# LongLedPcb.net
KiCad netlist of a schematic drawn in Altium Designer
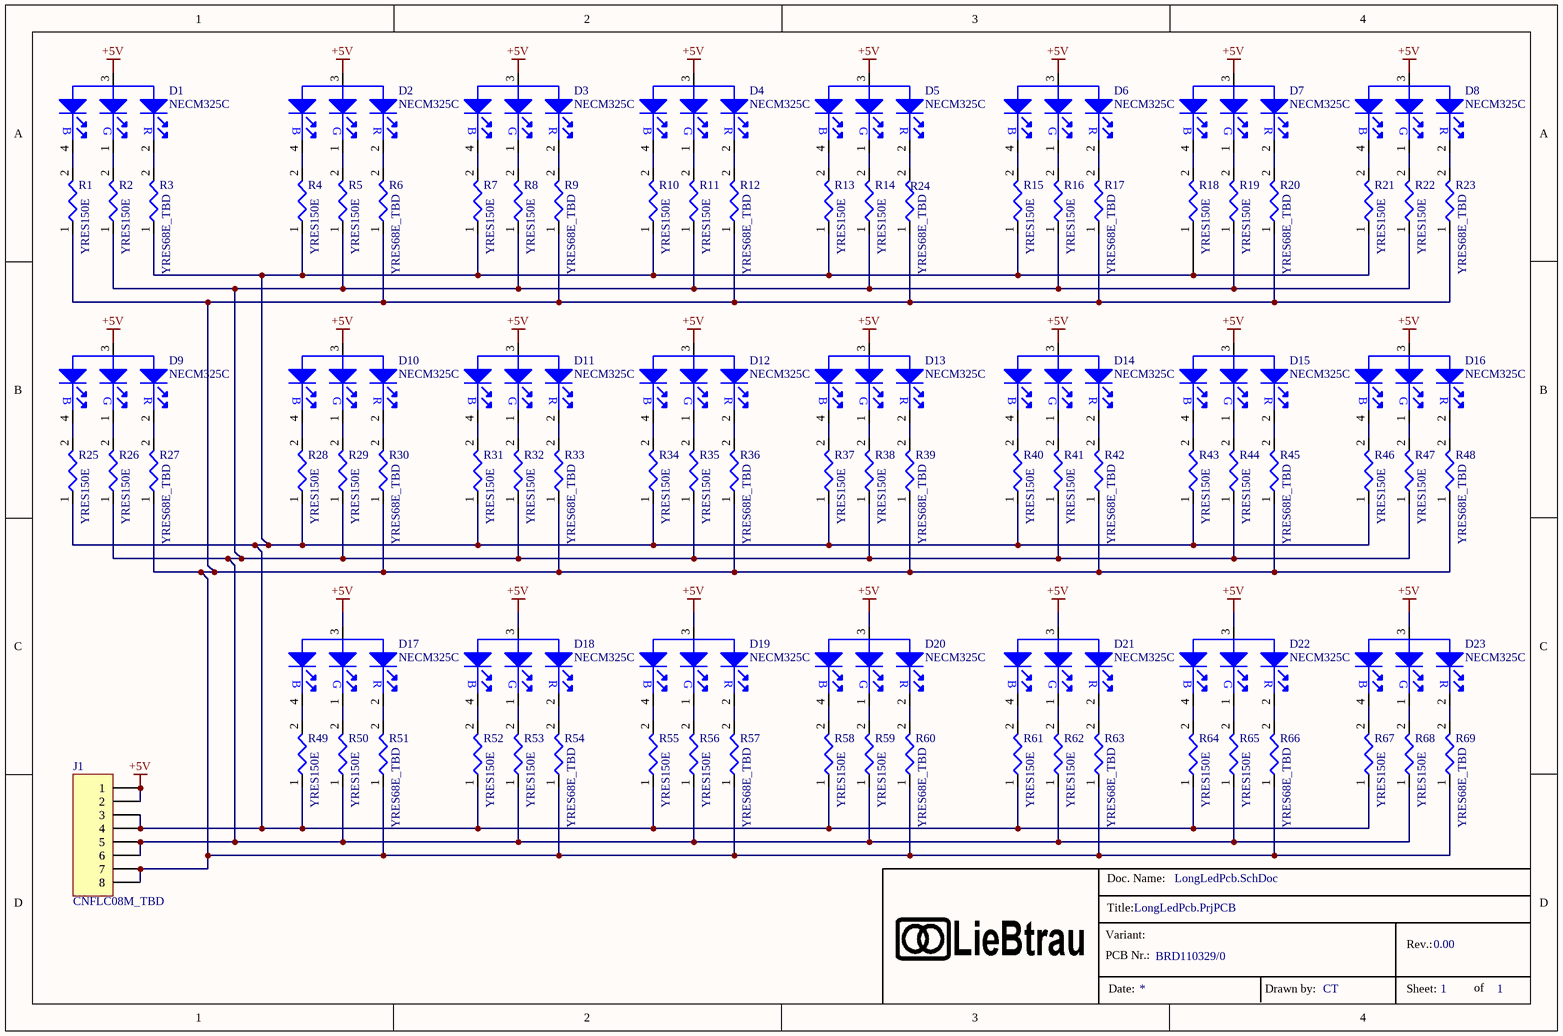
[diagram p0: LongLedPcb.SchDoc]

(export (version "E")
  (design (tool "Eeschema 10.0.6"))
  (components
    (comp (ref "D1")
      (value "NECM325C")
      (footprint "D_NECM325C")
      (libsource (lib "Testing") (part "D_LED_RGB"))
    )
    (comp (ref "D2")
      (value "NECM325C")
      (footprint "D_NECM325C")
      (libsource (lib "Testing") (part "D_LED_RGB"))
    )
    (comp (ref "D3")
      (value "NECM325C")
      (footprint "D_NECM325C")
      (libsource (lib "Testing") (part "D_LED_RGB"))
    )
    (comp (ref "D4")
      (value "NECM325C")
      (footprint "D_NECM325C")
      (libsource (lib "Testing") (part "D_LED_RGB"))
    )
    (comp (ref "D5")
      (value "NECM325C")
      (footprint "D_NECM325C")
      (libsource (lib "Testing") (part "D_LED_RGB"))
    )
    (comp (ref "D6")
      (value "NECM325C")
      (footprint "D_NECM325C")
      (libsource (lib "Testing") (part "D_LED_RGB"))
    )
    (comp (ref "D7")
      (value "NECM325C")
      (footprint "D_NECM325C")
      (libsource (lib "Testing") (part "D_LED_RGB"))
    )
    (comp (ref "D8")
      (value "NECM325C")
      (footprint "D_NECM325C")
      (libsource (lib "Testing") (part "D_LED_RGB"))
    )
    (comp (ref "D9")
      (value "NECM325C")
      (footprint "D_NECM325C")
      (libsource (lib "Testing") (part "D_LED_RGB"))
    )
    (comp (ref "D10")
      (value "NECM325C")
      (footprint "D_NECM325C")
      (libsource (lib "Testing") (part "D_LED_RGB"))
    )
    (comp (ref "D11")
      (value "NECM325C")
      (footprint "D_NECM325C")
      (libsource (lib "Testing") (part "D_LED_RGB"))
    )
    (comp (ref "D12")
      (value "NECM325C")
      (footprint "D_NECM325C")
      (libsource (lib "Testing") (part "D_LED_RGB"))
    )
    (comp (ref "D13")
      (value "NECM325C")
      (footprint "D_NECM325C")
      (libsource (lib "Testing") (part "D_LED_RGB"))
    )
    (comp (ref "D14")
      (value "NECM325C")
      (footprint "D_NECM325C")
      (libsource (lib "Testing") (part "D_LED_RGB"))
    )
    (comp (ref "D15")
      (value "NECM325C")
      (footprint "D_NECM325C")
      (libsource (lib "Testing") (part "D_LED_RGB"))
    )
    (comp (ref "D16")
      (value "NECM325C")
      (footprint "D_NECM325C")
      (libsource (lib "Testing") (part "D_LED_RGB"))
    )
    (comp (ref "D17")
      (value "NECM325C")
      (footprint "D_NECM325C")
      (libsource (lib "Testing") (part "D_LED_RGB"))
    )
    (comp (ref "D18")
      (value "NECM325C")
      (footprint "D_NECM325C")
      (libsource (lib "Testing") (part "D_LED_RGB"))
    )
    (comp (ref "D19")
      (value "NECM325C")
      (footprint "D_NECM325C")
      (libsource (lib "Testing") (part "D_LED_RGB"))
    )
    (comp (ref "D20")
      (value "NECM325C")
      (footprint "D_NECM325C")
      (libsource (lib "Testing") (part "D_LED_RGB"))
    )
    (comp (ref "D21")
      (value "NECM325C")
      (footprint "D_NECM325C")
      (libsource (lib "Testing") (part "D_LED_RGB"))
    )
    (comp (ref "D22")
      (value "NECM325C")
      (footprint "D_NECM325C")
      (libsource (lib "Testing") (part "D_LED_RGB"))
    )
    (comp (ref "D23")
      (value "NECM325C")
      (footprint "D_NECM325C")
      (libsource (lib "Testing") (part "D_LED_RGB"))
    )
    (comp (ref "J1")
      (value "CNFLC08M_TBD")
      (footprint "J_215079-8")
      (fields (field (name "PART NUMBER") "CNFLC08F_TBD"))
      (libsource (lib "Testing") (part "J_8P"))
    )
    (comp (ref "R1")
      (value "YRES150E")
      (footprint "R_1206")
      (description "Resistor")
      (libsource (lib "Testing") (part "R_RES"))
    )
    (comp (ref "R2")
      (value "YRES150E")
      (footprint "R_1206")
      (description "Resistor")
      (libsource (lib "Testing") (part "R_RES"))
    )
    (comp (ref "R3")
      (value "YRES68E_TBD")
      (footprint "R_1206")
      (description "Resistor")
      (libsource (lib "Testing") (part "R_RES"))
    )
    (comp (ref "R4")
      (value "YRES150E")
      (footprint "R_1206")
      (description "Resistor")
      (libsource (lib "Testing") (part "R_RES"))
    )
    (comp (ref "R5")
      (value "YRES150E")
      (footprint "R_1206")
      (description "Resistor")
      (libsource (lib "Testing") (part "R_RES"))
    )
    (comp (ref "R6")
      (value "YRES68E_TBD")
      (footprint "R_1206")
      (description "Resistor")
      (libsource (lib "Testing") (part "R_RES"))
    )
    (comp (ref "R7")
      (value "YRES150E")
      (footprint "R_1206")
      (description "Resistor")
      (libsource (lib "Testing") (part "R_RES"))
    )
    (comp (ref "R8")
      (value "YRES150E")
      (footprint "R_1206")
      (description "Resistor")
      (libsource (lib "Testing") (part "R_RES"))
    )
    (comp (ref "R9")
      (value "YRES68E_TBD")
      (footprint "R_1206")
      (description "Resistor")
      (libsource (lib "Testing") (part "R_RES"))
    )
    (comp (ref "R10")
      (value "YRES150E")
      (footprint "R_1206")
      (description "Resistor")
      (libsource (lib "Testing") (part "R_RES"))
    )
    (comp (ref "R11")
      (value "YRES150E")
      (footprint "R_1206")
      (description "Resistor")
      (libsource (lib "Testing") (part "R_RES"))
    )
    (comp (ref "R12")
      (value "YRES68E_TBD")
      (footprint "R_1206")
      (description "Resistor")
      (libsource (lib "Testing") (part "R_RES"))
    )
    (comp (ref "R13")
      (value "YRES150E")
      (footprint "R_1206")
      (description "Resistor")
      (libsource (lib "Testing") (part "R_RES"))
    )
    (comp (ref "R14")
      (value "YRES150E")
      (footprint "R_1206")
      (description "Resistor")
      (libsource (lib "Testing") (part "R_RES"))
    )
    (comp (ref "R15")
      (value "YRES150E")
      (footprint "R_1206")
      (description "Resistor")
      (libsource (lib "Testing") (part "R_RES"))
    )
    (comp (ref "R16")
      (value "YRES150E")
      (footprint "R_1206")
      (description "Resistor")
      (libsource (lib "Testing") (part "R_RES"))
    )
    (comp (ref "R17")
      (value "YRES68E_TBD")
      (footprint "R_1206")
      (description "Resistor")
      (libsource (lib "Testing") (part "R_RES"))
    )
    (comp (ref "R18")
      (value "YRES150E")
      (footprint "R_1206")
      (description "Resistor")
      (libsource (lib "Testing") (part "R_RES"))
    )
    (comp (ref "R19")
      (value "YRES150E")
      (footprint "R_1206")
      (description "Resistor")
      (libsource (lib "Testing") (part "R_RES"))
    )
    (comp (ref "R20")
      (value "YRES68E_TBD")
      (footprint "R_1206")
      (description "Resistor")
      (libsource (lib "Testing") (part "R_RES"))
    )
    (comp (ref "R21")
      (value "YRES150E")
      (footprint "R_1206")
      (description "Resistor")
      (libsource (lib "Testing") (part "R_RES"))
    )
    (comp (ref "R22")
      (value "YRES150E")
      (footprint "R_1206")
      (description "Resistor")
      (libsource (lib "Testing") (part "R_RES"))
    )
    (comp (ref "R23")
      (value "YRES68E_TBD")
      (footprint "R_1206")
      (description "Resistor")
      (libsource (lib "Testing") (part "R_RES"))
    )
    (comp (ref "R24")
      (value "YRES68E_TBD")
      (footprint "R_1206")
      (description "Resistor")
      (libsource (lib "Testing") (part "R_RES"))
    )
    (comp (ref "R25")
      (value "YRES150E")
      (footprint "R_1206")
      (description "Resistor")
      (libsource (lib "Testing") (part "R_RES"))
    )
    (comp (ref "R26")
      (value "YRES150E")
      (footprint "R_1206")
      (description "Resistor")
      (libsource (lib "Testing") (part "R_RES"))
    )
    (comp (ref "R27")
      (value "YRES68E_TBD")
      (footprint "R_1206")
      (description "Resistor")
      (libsource (lib "Testing") (part "R_RES"))
    )
    (comp (ref "R28")
      (value "YRES150E")
      (footprint "R_1206")
      (description "Resistor")
      (libsource (lib "Testing") (part "R_RES"))
    )
    (comp (ref "R29")
      (value "YRES150E")
      (footprint "R_1206")
      (description "Resistor")
      (libsource (lib "Testing") (part "R_RES"))
    )
    (comp (ref "R30")
      (value "YRES68E_TBD")
      (footprint "R_1206")
      (description "Resistor")
      (libsource (lib "Testing") (part "R_RES"))
    )
    (comp (ref "R31")
      (value "YRES150E")
      (footprint "R_1206")
      (description "Resistor")
      (libsource (lib "Testing") (part "R_RES"))
    )
    (comp (ref "R32")
      (value "YRES150E")
      (footprint "R_1206")
      (description "Resistor")
      (libsource (lib "Testing") (part "R_RES"))
    )
    (comp (ref "R33")
      (value "YRES68E_TBD")
      (footprint "R_1206")
      (description "Resistor")
      (libsource (lib "Testing") (part "R_RES"))
    )
    (comp (ref "R34")
      (value "YRES150E")
      (footprint "R_1206")
      (description "Resistor")
      (libsource (lib "Testing") (part "R_RES"))
    )
    (comp (ref "R35")
      (value "YRES150E")
      (footprint "R_1206")
      (description "Resistor")
      (libsource (lib "Testing") (part "R_RES"))
    )
    (comp (ref "R36")
      (value "YRES68E_TBD")
      (footprint "R_1206")
      (description "Resistor")
      (libsource (lib "Testing") (part "R_RES"))
    )
    (comp (ref "R37")
      (value "YRES150E")
      (footprint "R_1206")
      (description "Resistor")
      (libsource (lib "Testing") (part "R_RES"))
    )
    (comp (ref "R38")
      (value "YRES150E")
      (footprint "R_1206")
      (description "Resistor")
      (libsource (lib "Testing") (part "R_RES"))
    )
    (comp (ref "R39")
      (value "YRES68E_TBD")
      (footprint "R_1206")
      (description "Resistor")
      (libsource (lib "Testing") (part "R_RES"))
    )
    (comp (ref "R40")
      (value "YRES150E")
      (footprint "R_1206")
      (description "Resistor")
      (libsource (lib "Testing") (part "R_RES"))
    )
    (comp (ref "R41")
      (value "YRES150E")
      (footprint "R_1206")
      (description "Resistor")
      (libsource (lib "Testing") (part "R_RES"))
    )
    (comp (ref "R42")
      (value "YRES68E_TBD")
      (footprint "R_1206")
      (description "Resistor")
      (libsource (lib "Testing") (part "R_RES"))
    )
    (comp (ref "R43")
      (value "YRES150E")
      (footprint "R_1206")
      (description "Resistor")
      (libsource (lib "Testing") (part "R_RES"))
    )
    (comp (ref "R44")
      (value "YRES150E")
      (footprint "R_1206")
      (description "Resistor")
      (libsource (lib "Testing") (part "R_RES"))
    )
    (comp (ref "R45")
      (value "YRES68E_TBD")
      (footprint "R_1206")
      (description "Resistor")
      (libsource (lib "Testing") (part "R_RES"))
    )
    (comp (ref "R46")
      (value "YRES150E")
      (footprint "R_1206")
      (description "Resistor")
      (libsource (lib "Testing") (part "R_RES"))
    )
    (comp (ref "R47")
      (value "YRES150E")
      (footprint "R_1206")
      (description "Resistor")
      (libsource (lib "Testing") (part "R_RES"))
    )
    (comp (ref "R48")
      (value "YRES68E_TBD")
      (footprint "R_1206")
      (description "Resistor")
      (libsource (lib "Testing") (part "R_RES"))
    )
    (comp (ref "R49")
      (value "YRES150E")
      (footprint "R_1206")
      (description "Resistor")
      (libsource (lib "Testing") (part "R_RES"))
    )
    (comp (ref "R50")
      (value "YRES150E")
      (footprint "R_1206")
      (description "Resistor")
      (libsource (lib "Testing") (part "R_RES"))
    )
    (comp (ref "R51")
      (value "YRES68E_TBD")
      (footprint "R_1206")
      (description "Resistor")
      (libsource (lib "Testing") (part "R_RES"))
    )
    (comp (ref "R52")
      (value "YRES150E")
      (footprint "R_1206")
      (description "Resistor")
      (libsource (lib "Testing") (part "R_RES"))
    )
    (comp (ref "R53")
      (value "YRES150E")
      (footprint "R_1206")
      (description "Resistor")
      (libsource (lib "Testing") (part "R_RES"))
    )
    (comp (ref "R54")
      (value "YRES68E_TBD")
      (footprint "R_1206")
      (description "Resistor")
      (libsource (lib "Testing") (part "R_RES"))
    )
    (comp (ref "R55")
      (value "YRES150E")
      (footprint "R_1206")
      (description "Resistor")
      (libsource (lib "Testing") (part "R_RES"))
    )
    (comp (ref "R56")
      (value "YRES150E")
      (footprint "R_1206")
      (description "Resistor")
      (libsource (lib "Testing") (part "R_RES"))
    )
    (comp (ref "R57")
      (value "YRES68E_TBD")
      (footprint "R_1206")
      (description "Resistor")
      (libsource (lib "Testing") (part "R_RES"))
    )
    (comp (ref "R58")
      (value "YRES150E")
      (footprint "R_1206")
      (description "Resistor")
      (libsource (lib "Testing") (part "R_RES"))
    )
    (comp (ref "R59")
      (value "YRES150E")
      (footprint "R_1206")
      (description "Resistor")
      (libsource (lib "Testing") (part "R_RES"))
    )
    (comp (ref "R60")
      (value "YRES68E_TBD")
      (footprint "R_1206")
      (description "Resistor")
      (libsource (lib "Testing") (part "R_RES"))
    )
    (comp (ref "R61")
      (value "YRES150E")
      (footprint "R_1206")
      (description "Resistor")
      (libsource (lib "Testing") (part "R_RES"))
    )
    (comp (ref "R62")
      (value "YRES150E")
      (footprint "R_1206")
      (description "Resistor")
      (libsource (lib "Testing") (part "R_RES"))
    )
    (comp (ref "R63")
      (value "YRES68E_TBD")
      (footprint "R_1206")
      (description "Resistor")
      (libsource (lib "Testing") (part "R_RES"))
    )
    (comp (ref "R64")
      (value "YRES150E")
      (footprint "R_1206")
      (description "Resistor")
      (libsource (lib "Testing") (part "R_RES"))
    )
    (comp (ref "R65")
      (value "YRES150E")
      (footprint "R_1206")
      (description "Resistor")
      (libsource (lib "Testing") (part "R_RES"))
    )
    (comp (ref "R66")
      (value "YRES68E_TBD")
      (footprint "R_1206")
      (description "Resistor")
      (libsource (lib "Testing") (part "R_RES"))
    )
    (comp (ref "R67")
      (value "YRES150E")
      (footprint "R_1206")
      (description "Resistor")
      (libsource (lib "Testing") (part "R_RES"))
    )
    (comp (ref "R68")
      (value "YRES150E")
      (footprint "R_1206")
      (description "Resistor")
      (libsource (lib "Testing") (part "R_RES"))
    )
    (comp (ref "R69")
      (value "YRES68E_TBD")
      (footprint "R_1206")
      (description "Resistor")
      (libsource (lib "Testing") (part "R_RES"))
    )
  )
  (nets
    (net (code "1") (name "+5V") (class "Default")
      (node (ref "D1") (pin "3") (pinfunction "A_3") (pintype "passive"))
      (node (ref "D10") (pin "3") (pinfunction "A_3") (pintype "passive"))
      (node (ref "D11") (pin "3") (pinfunction "A_3") (pintype "passive"))
      (node (ref "D12") (pin "3") (pinfunction "A_3") (pintype "passive"))
      (node (ref "D13") (pin "3") (pinfunction "A_3") (pintype "passive"))
      (node (ref "D14") (pin "3") (pinfunction "A_3") (pintype "passive"))
      (node (ref "D15") (pin "3") (pinfunction "A_3") (pintype "passive"))
      (node (ref "D16") (pin "3") (pinfunction "A_3") (pintype "passive"))
      (node (ref "D17") (pin "3") (pinfunction "A_3") (pintype "passive"))
      (node (ref "D18") (pin "3") (pinfunction "A_3") (pintype "passive"))
      (node (ref "D19") (pin "3") (pinfunction "A_3") (pintype "passive"))
      (node (ref "D2") (pin "3") (pinfunction "A_3") (pintype "passive"))
      (node (ref "D20") (pin "3") (pinfunction "A_3") (pintype "passive"))
      (node (ref "D21") (pin "3") (pinfunction "A_3") (pintype "passive"))
      (node (ref "D22") (pin "3") (pinfunction "A_3") (pintype "passive"))
      (node (ref "D23") (pin "3") (pinfunction "A_3") (pintype "passive"))
      (node (ref "D3") (pin "3") (pinfunction "A_3") (pintype "passive"))
      (node (ref "D4") (pin "3") (pinfunction "A_3") (pintype "passive"))
      (node (ref "D5") (pin "3") (pinfunction "A_3") (pintype "passive"))
      (node (ref "D6") (pin "3") (pinfunction "A_3") (pintype "passive"))
      (node (ref "D7") (pin "3") (pinfunction "A_3") (pintype "passive"))
      (node (ref "D8") (pin "3") (pinfunction "A_3") (pintype "passive"))
      (node (ref "D9") (pin "3") (pinfunction "A_3") (pintype "passive"))
      (node (ref "J1") (pin "1") (pinfunction "1_1") (pintype "passive"))
      (node (ref "J1") (pin "2") (pinfunction "2_2") (pintype "passive"))
    )
    (net (code "2") (name "Net-(D1-C-Pad1)") (class "Default")
      (node (ref "D1") (pin "1") (pinfunction "C_1") (pintype "passive"))
      (node (ref "R2") (pin "2") (pinfunction "2_2") (pintype "passive"))
    )
    (net (code "3") (name "Net-(D1-C-Pad2)") (class "Default")
      (node (ref "D1") (pin "2") (pinfunction "C_2") (pintype "passive"))
      (node (ref "R3") (pin "2") (pinfunction "2_2") (pintype "passive"))
    )
    (net (code "4") (name "Net-(D1-C-Pad4)") (class "Default")
      (node (ref "D1") (pin "4") (pinfunction "C_4") (pintype "passive"))
      (node (ref "R1") (pin "2") (pinfunction "2_2") (pintype "passive"))
    )
    (net (code "5") (name "Net-(D2-C-Pad1)") (class "Default")
      (node (ref "D2") (pin "1") (pinfunction "C_1") (pintype "passive"))
      (node (ref "R5") (pin "2") (pinfunction "2_2") (pintype "passive"))
    )
    (net (code "6") (name "Net-(D2-C-Pad2)") (class "Default")
      (node (ref "D2") (pin "2") (pinfunction "C_2") (pintype "passive"))
      (node (ref "R6") (pin "2") (pinfunction "2_2") (pintype "passive"))
    )
    (net (code "7") (name "Net-(D2-C-Pad4)") (class "Default")
      (node (ref "D2") (pin "4") (pinfunction "C_4") (pintype "passive"))
      (node (ref "R4") (pin "2") (pinfunction "2_2") (pintype "passive"))
    )
    (net (code "8") (name "Net-(D3-C-Pad1)") (class "Default")
      (node (ref "D3") (pin "1") (pinfunction "C_1") (pintype "passive"))
      (node (ref "R8") (pin "2") (pinfunction "2_2") (pintype "passive"))
    )
    (net (code "9") (name "Net-(D3-C-Pad2)") (class "Default")
      (node (ref "D3") (pin "2") (pinfunction "C_2") (pintype "passive"))
      (node (ref "R9") (pin "2") (pinfunction "2_2") (pintype "passive"))
    )
    (net (code "10") (name "Net-(D3-C-Pad4)") (class "Default")
      (node (ref "D3") (pin "4") (pinfunction "C_4") (pintype "passive"))
      (node (ref "R7") (pin "2") (pinfunction "2_2") (pintype "passive"))
    )
    (net (code "11") (name "Net-(D4-C-Pad1)") (class "Default")
      (node (ref "D4") (pin "1") (pinfunction "C_1") (pintype "passive"))
      (node (ref "R11") (pin "2") (pinfunction "2_2") (pintype "passive"))
    )
    (net (code "12") (name "Net-(D4-C-Pad2)") (class "Default")
      (node (ref "D4") (pin "2") (pinfunction "C_2") (pintype "passive"))
      (node (ref "R12") (pin "2") (pinfunction "2_2") (pintype "passive"))
    )
    (net (code "13") (name "Net-(D4-C-Pad4)") (class "Default")
      (node (ref "D4") (pin "4") (pinfunction "C_4") (pintype "passive"))
      (node (ref "R10") (pin "2") (pinfunction "2_2") (pintype "passive"))
    )
    (net (code "14") (name "Net-(D5-C-Pad1)") (class "Default")
      (node (ref "D5") (pin "1") (pinfunction "C_1") (pintype "passive"))
      (node (ref "R14") (pin "2") (pinfunction "2_2") (pintype "passive"))
    )
    (net (code "15") (name "Net-(D5-C-Pad2)") (class "Default")
      (node (ref "D5") (pin "2") (pinfunction "C_2") (pintype "passive"))
      (node (ref "R24") (pin "2") (pinfunction "2_2") (pintype "passive"))
    )
    (net (code "16") (name "Net-(D5-C-Pad4)") (class "Default")
      (node (ref "D5") (pin "4") (pinfunction "C_4") (pintype "passive"))
      (node (ref "R13") (pin "2") (pinfunction "2_2") (pintype "passive"))
    )
    (net (code "17") (name "Net-(D6-C-Pad1)") (class "Default")
      (node (ref "D6") (pin "1") (pinfunction "C_1") (pintype "passive"))
      (node (ref "R16") (pin "2") (pinfunction "2_2") (pintype "passive"))
    )
    (net (code "18") (name "Net-(D6-C-Pad2)") (class "Default")
      (node (ref "D6") (pin "2") (pinfunction "C_2") (pintype "passive"))
      (node (ref "R17") (pin "2") (pinfunction "2_2") (pintype "passive"))
    )
    (net (code "19") (name "Net-(D6-C-Pad4)") (class "Default")
      (node (ref "D6") (pin "4") (pinfunction "C_4") (pintype "passive"))
      (node (ref "R15") (pin "2") (pinfunction "2_2") (pintype "passive"))
    )
    (net (code "20") (name "Net-(D7-C-Pad1)") (class "Default")
      (node (ref "D7") (pin "1") (pinfunction "C_1") (pintype "passive"))
      (node (ref "R19") (pin "2") (pinfunction "2_2") (pintype "passive"))
    )
    (net (code "21") (name "Net-(D7-C-Pad2)") (class "Default")
      (node (ref "D7") (pin "2") (pinfunction "C_2") (pintype "passive"))
      (node (ref "R20") (pin "2") (pinfunction "2_2") (pintype "passive"))
    )
    (net (code "22") (name "Net-(D7-C-Pad4)") (class "Default")
      (node (ref "D7") (pin "4") (pinfunction "C_4") (pintype "passive"))
      (node (ref "R18") (pin "2") (pinfunction "2_2") (pintype "passive"))
    )
    (net (code "23") (name "Net-(D8-C-Pad1)") (class "Default")
      (node (ref "D8") (pin "1") (pinfunction "C_1") (pintype "passive"))
      (node (ref "R22") (pin "2") (pinfunction "2_2") (pintype "passive"))
    )
    (net (code "24") (name "Net-(D8-C-Pad2)") (class "Default")
      (node (ref "D8") (pin "2") (pinfunction "C_2") (pintype "passive"))
      (node (ref "R23") (pin "2") (pinfunction "2_2") (pintype "passive"))
    )
    (net (code "25") (name "Net-(D8-C-Pad4)") (class "Default")
      (node (ref "D8") (pin "4") (pinfunction "C_4") (pintype "passive"))
      (node (ref "R21") (pin "2") (pinfunction "2_2") (pintype "passive"))
    )
    (net (code "26") (name "Net-(D9-C-Pad1)") (class "Default")
      (node (ref "D9") (pin "1") (pinfunction "C_1") (pintype "passive"))
      (node (ref "R26") (pin "2") (pinfunction "2_2") (pintype "passive"))
    )
    (net (code "27") (name "Net-(D9-C-Pad2)") (class "Default")
      (node (ref "D9") (pin "2") (pinfunction "C_2") (pintype "passive"))
      (node (ref "R27") (pin "2") (pinfunction "2_2") (pintype "passive"))
    )
    (net (code "28") (name "Net-(D9-C-Pad4)") (class "Default")
      (node (ref "D9") (pin "4") (pinfunction "C_4") (pintype "passive"))
      (node (ref "R25") (pin "2") (pinfunction "2_2") (pintype "passive"))
    )
    (net (code "29") (name "Net-(D10-C-Pad1)") (class "Default")
      (node (ref "D10") (pin "1") (pinfunction "C_1") (pintype "passive"))
      (node (ref "R29") (pin "2") (pinfunction "2_2") (pintype "passive"))
    )
    (net (code "30") (name "Net-(D10-C-Pad2)") (class "Default")
      (node (ref "D10") (pin "2") (pinfunction "C_2") (pintype "passive"))
      (node (ref "R30") (pin "2") (pinfunction "2_2") (pintype "passive"))
    )
    (net (code "31") (name "Net-(D10-C-Pad4)") (class "Default")
      (node (ref "D10") (pin "4") (pinfunction "C_4") (pintype "passive"))
      (node (ref "R28") (pin "2") (pinfunction "2_2") (pintype "passive"))
    )
    (net (code "32") (name "Net-(D11-C-Pad1)") (class "Default")
      (node (ref "D11") (pin "1") (pinfunction "C_1") (pintype "passive"))
      (node (ref "R32") (pin "2") (pinfunction "2_2") (pintype "passive"))
    )
    (net (code "33") (name "Net-(D11-C-Pad2)") (class "Default")
      (node (ref "D11") (pin "2") (pinfunction "C_2") (pintype "passive"))
      (node (ref "R33") (pin "2") (pinfunction "2_2") (pintype "passive"))
    )
    (net (code "34") (name "Net-(D11-C-Pad4)") (class "Default")
      (node (ref "D11") (pin "4") (pinfunction "C_4") (pintype "passive"))
      (node (ref "R31") (pin "2") (pinfunction "2_2") (pintype "passive"))
    )
    (net (code "35") (name "Net-(D12-C-Pad1)") (class "Default")
      (node (ref "D12") (pin "1") (pinfunction "C_1") (pintype "passive"))
      (node (ref "R35") (pin "2") (pinfunction "2_2") (pintype "passive"))
    )
    (net (code "36") (name "Net-(D12-C-Pad2)") (class "Default")
      (node (ref "D12") (pin "2") (pinfunction "C_2") (pintype "passive"))
      (node (ref "R36") (pin "2") (pinfunction "2_2") (pintype "passive"))
    )
    (net (code "37") (name "Net-(D12-C-Pad4)") (class "Default")
      (node (ref "D12") (pin "4") (pinfunction "C_4") (pintype "passive"))
      (node (ref "R34") (pin "2") (pinfunction "2_2") (pintype "passive"))
    )
    (net (code "38") (name "Net-(D13-C-Pad1)") (class "Default")
      (node (ref "D13") (pin "1") (pinfunction "C_1") (pintype "passive"))
      (node (ref "R38") (pin "2") (pinfunction "2_2") (pintype "passive"))
    )
    (net (code "39") (name "Net-(D13-C-Pad2)") (class "Default")
      (node (ref "D13") (pin "2") (pinfunction "C_2") (pintype "passive"))
      (node (ref "R39") (pin "2") (pinfunction "2_2") (pintype "passive"))
    )
    (net (code "40") (name "Net-(D13-C-Pad4)") (class "Default")
      (node (ref "D13") (pin "4") (pinfunction "C_4") (pintype "passive"))
      (node (ref "R37") (pin "2") (pinfunction "2_2") (pintype "passive"))
    )
    (net (code "41") (name "Net-(D14-C-Pad1)") (class "Default")
      (node (ref "D14") (pin "1") (pinfunction "C_1") (pintype "passive"))
      (node (ref "R41") (pin "2") (pinfunction "2_2") (pintype "passive"))
    )
    (net (code "42") (name "Net-(D14-C-Pad2)") (class "Default")
      (node (ref "D14") (pin "2") (pinfunction "C_2") (pintype "passive"))
      (node (ref "R42") (pin "2") (pinfunction "2_2") (pintype "passive"))
    )
    (net (code "43") (name "Net-(D14-C-Pad4)") (class "Default")
      (node (ref "D14") (pin "4") (pinfunction "C_4") (pintype "passive"))
      (node (ref "R40") (pin "2") (pinfunction "2_2") (pintype "passive"))
    )
    (net (code "44") (name "Net-(D15-C-Pad1)") (class "Default")
      (node (ref "D15") (pin "1") (pinfunction "C_1") (pintype "passive"))
      (node (ref "R44") (pin "2") (pinfunction "2_2") (pintype "passive"))
    )
    (net (code "45") (name "Net-(D15-C-Pad2)") (class "Default")
      (node (ref "D15") (pin "2") (pinfunction "C_2") (pintype "passive"))
      (node (ref "R45") (pin "2") (pinfunction "2_2") (pintype "passive"))
    )
    (net (code "46") (name "Net-(D15-C-Pad4)") (class "Default")
      (node (ref "D15") (pin "4") (pinfunction "C_4") (pintype "passive"))
      (node (ref "R43") (pin "2") (pinfunction "2_2") (pintype "passive"))
    )
    (net (code "47") (name "Net-(D16-C-Pad1)") (class "Default")
      (node (ref "D16") (pin "1") (pinfunction "C_1") (pintype "passive"))
      (node (ref "R47") (pin "2") (pinfunction "2_2") (pintype "passive"))
    )
    (net (code "48") (name "Net-(D16-C-Pad2)") (class "Default")
      (node (ref "D16") (pin "2") (pinfunction "C_2") (pintype "passive"))
      (node (ref "R48") (pin "2") (pinfunction "2_2") (pintype "passive"))
    )
    (net (code "49") (name "Net-(D16-C-Pad4)") (class "Default")
      (node (ref "D16") (pin "4") (pinfunction "C_4") (pintype "passive"))
      (node (ref "R46") (pin "2") (pinfunction "2_2") (pintype "passive"))
    )
    (net (code "50") (name "Net-(D17-C-Pad1)") (class "Default")
      (node (ref "D17") (pin "1") (pinfunction "C_1") (pintype "passive"))
      (node (ref "R50") (pin "2") (pinfunction "2_2") (pintype "passive"))
    )
    (net (code "51") (name "Net-(D17-C-Pad2)") (class "Default")
      (node (ref "D17") (pin "2") (pinfunction "C_2") (pintype "passive"))
      (node (ref "R51") (pin "2") (pinfunction "2_2") (pintype "passive"))
    )
    (net (code "52") (name "Net-(D17-C-Pad4)") (class "Default")
      (node (ref "D17") (pin "4") (pinfunction "C_4") (pintype "passive"))
      (node (ref "R49") (pin "2") (pinfunction "2_2") (pintype "passive"))
    )
    (net (code "53") (name "Net-(D18-C-Pad1)") (class "Default")
      (node (ref "D18") (pin "1") (pinfunction "C_1") (pintype "passive"))
      (node (ref "R53") (pin "2") (pinfunction "2_2") (pintype "passive"))
    )
    (net (code "54") (name "Net-(D18-C-Pad2)") (class "Default")
      (node (ref "D18") (pin "2") (pinfunction "C_2") (pintype "passive"))
      (node (ref "R54") (pin "2") (pinfunction "2_2") (pintype "passive"))
    )
    (net (code "55") (name "Net-(D18-C-Pad4)") (class "Default")
      (node (ref "D18") (pin "4") (pinfunction "C_4") (pintype "passive"))
      (node (ref "R52") (pin "2") (pinfunction "2_2") (pintype "passive"))
    )
    (net (code "56") (name "Net-(D19-C-Pad1)") (class "Default")
      (node (ref "D19") (pin "1") (pinfunction "C_1") (pintype "passive"))
      (node (ref "R56") (pin "2") (pinfunction "2_2") (pintype "passive"))
    )
    (net (code "57") (name "Net-(D19-C-Pad2)") (class "Default")
      (node (ref "D19") (pin "2") (pinfunction "C_2") (pintype "passive"))
      (node (ref "R57") (pin "2") (pinfunction "2_2") (pintype "passive"))
    )
    (net (code "58") (name "Net-(D19-C-Pad4)") (class "Default")
      (node (ref "D19") (pin "4") (pinfunction "C_4") (pintype "passive"))
      (node (ref "R55") (pin "2") (pinfunction "2_2") (pintype "passive"))
    )
    (net (code "59") (name "Net-(D20-C-Pad1)") (class "Default")
      (node (ref "D20") (pin "1") (pinfunction "C_1") (pintype "passive"))
      (node (ref "R59") (pin "2") (pinfunction "2_2") (pintype "passive"))
    )
    (net (code "60") (name "Net-(D20-C-Pad2)") (class "Default")
      (node (ref "D20") (pin "2") (pinfunction "C_2") (pintype "passive"))
      (node (ref "R60") (pin "2") (pinfunction "2_2") (pintype "passive"))
    )
    (net (code "61") (name "Net-(D20-C-Pad4)") (class "Default")
      (node (ref "D20") (pin "4") (pinfunction "C_4") (pintype "passive"))
      (node (ref "R58") (pin "2") (pinfunction "2_2") (pintype "passive"))
    )
    (net (code "62") (name "Net-(D21-C-Pad1)") (class "Default")
      (node (ref "D21") (pin "1") (pinfunction "C_1") (pintype "passive"))
      (node (ref "R62") (pin "2") (pinfunction "2_2") (pintype "passive"))
    )
    (net (code "63") (name "Net-(D21-C-Pad2)") (class "Default")
      (node (ref "D21") (pin "2") (pinfunction "C_2") (pintype "passive"))
      (node (ref "R63") (pin "2") (pinfunction "2_2") (pintype "passive"))
    )
    (net (code "64") (name "Net-(D21-C-Pad4)") (class "Default")
      (node (ref "D21") (pin "4") (pinfunction "C_4") (pintype "passive"))
      (node (ref "R61") (pin "2") (pinfunction "2_2") (pintype "passive"))
    )
    (net (code "65") (name "Net-(D22-C-Pad1)") (class "Default")
      (node (ref "D22") (pin "1") (pinfunction "C_1") (pintype "passive"))
      (node (ref "R65") (pin "2") (pinfunction "2_2") (pintype "passive"))
    )
    (net (code "66") (name "Net-(D22-C-Pad2)") (class "Default")
      (node (ref "D22") (pin "2") (pinfunction "C_2") (pintype "passive"))
      (node (ref "R66") (pin "2") (pinfunction "2_2") (pintype "passive"))
    )
    (net (code "67") (name "Net-(D22-C-Pad4)") (class "Default")
      (node (ref "D22") (pin "4") (pinfunction "C_4") (pintype "passive"))
      (node (ref "R64") (pin "2") (pinfunction "2_2") (pintype "passive"))
    )
    (net (code "68") (name "Net-(D23-C-Pad1)") (class "Default")
      (node (ref "D23") (pin "1") (pinfunction "C_1") (pintype "passive"))
      (node (ref "R68") (pin "2") (pinfunction "2_2") (pintype "passive"))
    )
    (net (code "69") (name "Net-(D23-C-Pad2)") (class "Default")
      (node (ref "D23") (pin "2") (pinfunction "C_2") (pintype "passive"))
      (node (ref "R69") (pin "2") (pinfunction "2_2") (pintype "passive"))
    )
    (net (code "70") (name "Net-(D23-C-Pad4)") (class "Default")
      (node (ref "D23") (pin "4") (pinfunction "C_4") (pintype "passive"))
      (node (ref "R67") (pin "2") (pinfunction "2_2") (pintype "passive"))
    )
    (net (code "71") (name "Net-(J1-Pad3)") (class "Default")
      (node (ref "J1") (pin "3") (pinfunction "3_3") (pintype "passive"))
      (node (ref "J1") (pin "4") (pinfunction "4_4") (pintype "passive"))
      (node (ref "R10") (pin "1") (pinfunction "1_1") (pintype "passive"))
      (node (ref "R13") (pin "1") (pinfunction "1_1") (pintype "passive"))
      (node (ref "R15") (pin "1") (pinfunction "1_1") (pintype "passive"))
      (node (ref "R18") (pin "1") (pinfunction "1_1") (pintype "passive"))
      (node (ref "R21") (pin "1") (pinfunction "1_1") (pintype "passive"))
      (node (ref "R25") (pin "1") (pinfunction "1_1") (pintype "passive"))
      (node (ref "R28") (pin "1") (pinfunction "1_1") (pintype "passive"))
      (node (ref "R3") (pin "1") (pinfunction "1_1") (pintype "passive"))
      (node (ref "R31") (pin "1") (pinfunction "1_1") (pintype "passive"))
      (node (ref "R34") (pin "1") (pinfunction "1_1") (pintype "passive"))
      (node (ref "R37") (pin "1") (pinfunction "1_1") (pintype "passive"))
      (node (ref "R4") (pin "1") (pinfunction "1_1") (pintype "passive"))
      (node (ref "R40") (pin "1") (pinfunction "1_1") (pintype "passive"))
      (node (ref "R43") (pin "1") (pinfunction "1_1") (pintype "passive"))
      (node (ref "R46") (pin "1") (pinfunction "1_1") (pintype "passive"))
      (node (ref "R49") (pin "1") (pinfunction "1_1") (pintype "passive"))
      (node (ref "R52") (pin "1") (pinfunction "1_1") (pintype "passive"))
      (node (ref "R55") (pin "1") (pinfunction "1_1") (pintype "passive"))
      (node (ref "R58") (pin "1") (pinfunction "1_1") (pintype "passive"))
      (node (ref "R61") (pin "1") (pinfunction "1_1") (pintype "passive"))
      (node (ref "R64") (pin "1") (pinfunction "1_1") (pintype "passive"))
      (node (ref "R67") (pin "1") (pinfunction "1_1") (pintype "passive"))
      (node (ref "R7") (pin "1") (pinfunction "1_1") (pintype "passive"))
    )
    (net (code "72") (name "Net-(J1-Pad5)") (class "Default")
      (node (ref "J1") (pin "5") (pinfunction "5_5") (pintype "passive"))
      (node (ref "J1") (pin "6") (pinfunction "6_6") (pintype "passive"))
      (node (ref "R11") (pin "1") (pinfunction "1_1") (pintype "passive"))
      (node (ref "R14") (pin "1") (pinfunction "1_1") (pintype "passive"))
      (node (ref "R16") (pin "1") (pinfunction "1_1") (pintype "passive"))
      (node (ref "R19") (pin "1") (pinfunction "1_1") (pintype "passive"))
      (node (ref "R2") (pin "1") (pinfunction "1_1") (pintype "passive"))
      (node (ref "R22") (pin "1") (pinfunction "1_1") (pintype "passive"))
      (node (ref "R26") (pin "1") (pinfunction "1_1") (pintype "passive"))
      (node (ref "R29") (pin "1") (pinfunction "1_1") (pintype "passive"))
      (node (ref "R32") (pin "1") (pinfunction "1_1") (pintype "passive"))
      (node (ref "R35") (pin "1") (pinfunction "1_1") (pintype "passive"))
      (node (ref "R38") (pin "1") (pinfunction "1_1") (pintype "passive"))
      (node (ref "R41") (pin "1") (pinfunction "1_1") (pintype "passive"))
      (node (ref "R44") (pin "1") (pinfunction "1_1") (pintype "passive"))
      (node (ref "R47") (pin "1") (pinfunction "1_1") (pintype "passive"))
      (node (ref "R5") (pin "1") (pinfunction "1_1") (pintype "passive"))
      (node (ref "R50") (pin "1") (pinfunction "1_1") (pintype "passive"))
      (node (ref "R53") (pin "1") (pinfunction "1_1") (pintype "passive"))
      (node (ref "R56") (pin "1") (pinfunction "1_1") (pintype "passive"))
      (node (ref "R59") (pin "1") (pinfunction "1_1") (pintype "passive"))
      (node (ref "R62") (pin "1") (pinfunction "1_1") (pintype "passive"))
      (node (ref "R65") (pin "1") (pinfunction "1_1") (pintype "passive"))
      (node (ref "R68") (pin "1") (pinfunction "1_1") (pintype "passive"))
      (node (ref "R8") (pin "1") (pinfunction "1_1") (pintype "passive"))
    )
    (net (code "73") (name "Net-(J1-Pad7)") (class "Default")
      (node (ref "J1") (pin "7") (pinfunction "7_7") (pintype "passive"))
      (node (ref "J1") (pin "8") (pinfunction "8_8") (pintype "passive"))
      (node (ref "R1") (pin "1") (pinfunction "1_1") (pintype "passive"))
      (node (ref "R12") (pin "1") (pinfunction "1_1") (pintype "passive"))
      (node (ref "R17") (pin "1") (pinfunction "1_1") (pintype "passive"))
      (node (ref "R20") (pin "1") (pinfunction "1_1") (pintype "passive"))
      (node (ref "R23") (pin "1") (pinfunction "1_1") (pintype "passive"))
      (node (ref "R24") (pin "1") (pinfunction "1_1") (pintype "passive"))
      (node (ref "R27") (pin "1") (pinfunction "1_1") (pintype "passive"))
      (node (ref "R30") (pin "1") (pinfunction "1_1") (pintype "passive"))
      (node (ref "R33") (pin "1") (pinfunction "1_1") (pintype "passive"))
      (node (ref "R36") (pin "1") (pinfunction "1_1") (pintype "passive"))
      (node (ref "R39") (pin "1") (pinfunction "1_1") (pintype "passive"))
      (node (ref "R42") (pin "1") (pinfunction "1_1") (pintype "passive"))
      (node (ref "R45") (pin "1") (pinfunction "1_1") (pintype "passive"))
      (node (ref "R48") (pin "1") (pinfunction "1_1") (pintype "passive"))
      (node (ref "R51") (pin "1") (pinfunction "1_1") (pintype "passive"))
      (node (ref "R54") (pin "1") (pinfunction "1_1") (pintype "passive"))
      (node (ref "R57") (pin "1") (pinfunction "1_1") (pintype "passive"))
      (node (ref "R6") (pin "1") (pinfunction "1_1") (pintype "passive"))
      (node (ref "R60") (pin "1") (pinfunction "1_1") (pintype "passive"))
      (node (ref "R63") (pin "1") (pinfunction "1_1") (pintype "passive"))
      (node (ref "R66") (pin "1") (pinfunction "1_1") (pintype "passive"))
      (node (ref "R69") (pin "1") (pinfunction "1_1") (pintype "passive"))
      (node (ref "R9") (pin "1") (pinfunction "1_1") (pintype "passive"))
    )
  )
)
